# Sheet_2.net
KiCad netlist of a schematic drawn in Altium Designer
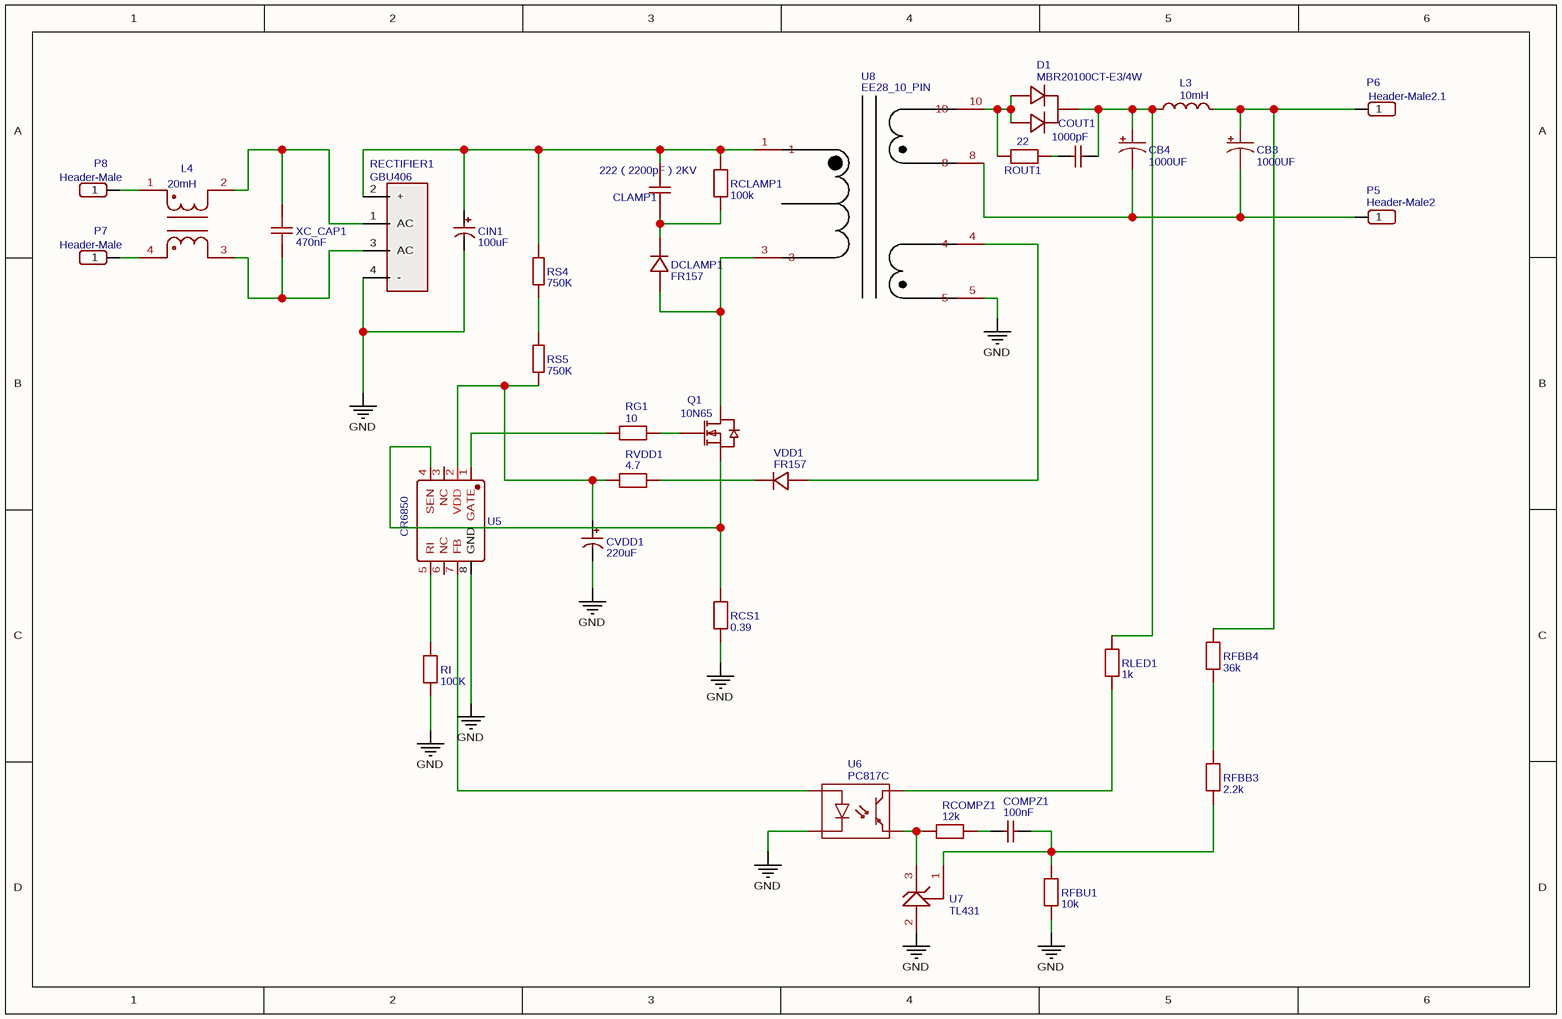
[diagram p0: Sheet_2.schdoc]

(export (version "E")
  (design (tool "Eeschema 10.0.6"))
  (components
    (comp (ref "CB3")
      (value "1000UF")
      (description "CAP-08070")
      (fields (field (name "CONTRIBUTOR") "SparkFun"))
      (libsource (lib "altium-import") (part "root_0_1000UF_"))
    )
    (comp (ref "CB4")
      (value "1000UF")
      (description "CAP-08070")
      (fields (field (name "CONTRIBUTOR") "SparkFun"))
      (libsource (lib "altium-import") (part "root_0_1000UF_"))
    )
    (comp (ref "CIN1")
      (value "100uF")
      (fields
        (field (name "BOM_MANUFACTURER PART") "400V 100uF 18X30")
        (field (name "BOM_SUPPLIER PART") "C2767")
      )
      (libsource (lib "altium-import") (part "root_3_100uF_"))
    )
    (comp (ref "CLAMP1")
      (value "222（2200pF）2KV")
      (fields (field (name "BOM_SUPPLIER PART") "C24926"))
      (libsource (lib "altium-import") (part "root_1_222（2200pF）2KV_"))
    )
    (comp (ref "COMPZ1")
      (value "100nF")
      (fields
        (field (name "BOM_MANUFACTURER PART") "104/100V 20%")
        (field (name "BOM_SUPPLIER PART") "C26856")
      )
      (libsource (lib "altium-import") (part "root_0_100nF_"))
    )
    (comp (ref "COUT1")
      (value "1000pF")
      (fields
        (field (name "BOM_MANUFACTURER PART") "102M 400V Y5V")
        (field (name "BOM_SUPPLIER PART") "C3704")
      )
      (libsource (lib "altium-import") (part "root_0_1000pF_"))
    )
    (comp (ref "CVDD1")
      (value "220uF")
      (fields (field (name "BOM_MANUFACTURER PART") "220uf/35V") (field (name "BOM_SUPPLIER PART") "C2063"))
      (libsource (lib "altium-import") (part "root_3_220uF_"))
    )
    (comp (ref "D1")
      (value "MBR20100CT-E3/4W")
      (fields (field (name "BOM_SUPPLIER PART") "C222466") (field (name "CONTRIBUTOR") "LCSC"))
      (libsource (lib "altium-import") (part "root_3_MBR20100CT-E3/4W_"))
    )
    (comp (ref "DCLAMP1")
      (value "FR157")
      (fields (field (name "BOM_SUPPLIER PART") "C2467"))
      (libsource (lib "altium-import") (part "root_1_FR157_"))
    )
    (comp (ref "L3")
      (value "10mH")
      (fields
        (field (name "BOM_MANUFACTURER PART") "VLU0608-103K")
        (field (name "BOM_SUPPLIER PART") "C72613")
      )
      (libsource (lib "altium-import") (part "root_0_10mH_"))
    )
    (comp (ref "L4")
      (value "20mH")
      (fields
        (field (name "BOM_SUPPLIER PART") "C148474")
        (field (name "BOM_MANUFACTURER PART") "UU9.8-10mH")
        (field (name "CONTRIBUTOR") "LCSC")
      )
      (libsource (lib "altium-import") (part "root_0_20mH_"))
    )
    (comp (ref "P5")
      (value "Header-Male2")
      (fields
        (field (name "BOM_MANUFACTURER PART") "Header-Male-2.54_1x1")
        (field (name "BOM_SUPPLIER PART") "C81276")
      )
      (libsource (lib "altium-import") (part "root_0_Header-Male2_"))
    )
    (comp (ref "P6")
      (value "Header-Male2.1")
      (fields
        (field (name "BOM_MANUFACTURER PART") "Header-Male-2.54_1x1")
        (field (name "BOM_SUPPLIER PART") "C81276")
      )
      (libsource (lib "altium-import") (part "root_0_Header-Male2.1_"))
    )
    (comp (ref "P7")
      (value "Header-Male")
      (fields
        (field (name "BOM_MANUFACTURER PART") "Header-Male-2.54_1x1")
        (field (name "BOM_SUPPLIER PART") "C81276")
      )
      (libsource (lib "altium-import") (part "root_2_Header-Male_"))
    )
    (comp (ref "P8")
      (value "Header-Male")
      (fields
        (field (name "BOM_MANUFACTURER PART") "Header-Male-2.54_1x1")
        (field (name "BOM_SUPPLIER PART") "C81276")
      )
      (libsource (lib "altium-import") (part "root_2_Header-Male_"))
    )
    (comp (ref "Q1")
      (value "10N65")
      (fields
        (field (name "BOM_MANUFACTURER PART") "10N65KL-TF3-T")
        (field (name "BOM_SUPPLIER PART") "C74166")
      )
      (libsource (lib "altium-import") (part "root_0_10N65_"))
    )
    (comp (ref "RCLAMP1") (value "100k") (libsource (lib "altium-import") (part "root_1_100k_")))
    (comp (ref "RCOMPZ1") (value "12k") (libsource (lib "altium-import") (part "root_0_12k_")))
    (comp (ref "RCS1") (value "0.39") (libsource (lib "altium-import") (part "root_1_0.39_")))
    (comp (ref "RECTIFIER1")
      (value "GBU406")
      (fields
        (field (name "BOM_MANUFACTURER PART") "GBU406 Rectifier bridge")
        (field (name "BOM_SUPPLIER PART") "C13432")
      )
      (libsource (lib "altium-import") (part "root_3_GBU406_"))
    )
    (comp (ref "RFBB3") (value "2.2k") (libsource (lib "altium-import") (part "root_1_2.2k_")))
    (comp (ref "RFBB4") (value "36k") (libsource (lib "altium-import") (part "root_1_36k_")))
    (comp (ref "RFBU1") (value "10k") (libsource (lib "altium-import") (part "root_1_10k_")))
    (comp (ref "RG1") (value "10") (libsource (lib "altium-import") (part "root_0_10_")))
    (comp (ref "RI") (value "100K") (libsource (lib "altium-import") (part "root_1_100K_")))
    (comp (ref "RLED1") (value "1k") (libsource (lib "altium-import") (part "root_1_1k_")))
    (comp (ref "ROUT1") (value "22") (libsource (lib "altium-import") (part "root_0_22_")))
    (comp (ref "RS4")
      (value "750K")
      (fields (field (name "BOM_SUPPLIER PART") "C119386") (field (name "CONTRIBUTOR") "LCSC"))
      (libsource (lib "altium-import") (part "root_1_750K_"))
    )
    (comp (ref "RS5")
      (value "750K")
      (fields (field (name "BOM_SUPPLIER PART") "C119386") (field (name "CONTRIBUTOR") "LCSC"))
      (libsource (lib "altium-import") (part "root_1_750K_"))
    )
    (comp (ref "RVDD1") (value "4.7") (libsource (lib "altium-import") (part "root_0_4.7_")))
    (comp (ref "U5")
      (value "CR6850")
      (fields
        (field (name "BOM_SUPPLIER PART") "C433346")
        (field (name "BOM_MANUFACTURER PART") "CR6850D")
        (field (name "CONTRIBUTOR") "LCSC")
      )
      (libsource (lib "altium-import") (part "root_3_CR6850_"))
    )
    (comp (ref "U6") (value "PC817C") (libsource (lib "altium-import") (part "root_0_PC817C_")))
    (comp (ref "U7")
      (value "TL431")
      (fields
        (field (name "BOM_MANUFACTURER PART") "TL431AILP")
        (field (name "BOM_SUPPLIER PART") "C72108")
        (field (name "CONTRIBUTOR") "LCSC")
      )
      (libsource (lib "altium-import") (part "root_1_TL431_"))
    )
    (comp (ref "U8")
      (value "EE28_10_PIN")
      (fields (field (name "BOM_SUPPLIER PART") "undefined") (field (name "CONTRIBUTOR") "kevwe"))
      (libsource (lib "altium-import") (part "root_0_EE28_10_PIN_"))
    )
    (comp (ref "VDD1")
      (value "FR157")
      (fields (field (name "BOM_SUPPLIER PART") "C2467"))
      (libsource (lib "altium-import") (part "root_2_FR157_"))
    )
    (comp (ref "XC_CAP1")
      (value "470nF")
      (fields (field (name "BOM_SUPPLIER PART") "C281974") (field (name "CONTRIBUTOR") "LCSC"))
      (libsource (lib "altium-import") (part "root_0_470nF_"))
    )
  )
  (nets
    (net (code "1") (name "GND") (class "Default")
      (node (ref "CIN1") (pin "2") (pinfunction "2_2") (pintype "passive"))
      (node (ref "CVDD1") (pin "2") (pinfunction "2_2") (pintype "passive"))
      (node (ref "RCS1") (pin "1") (pinfunction "1_1") (pintype "passive"))
      (node (ref "RECTIFIER1") (pin "4") (pinfunction "-_4") (pintype "passive"))
      (node (ref "RFBU1") (pin "1") (pinfunction "1_1") (pintype "passive"))
      (node (ref "RI") (pin "1") (pinfunction "1_1") (pintype "passive"))
      (node (ref "U5") (pin "8") (pinfunction "GND_8") (pintype "passive"))
      (node (ref "U6") (pin "2") (pinfunction "K_2") (pintype "passive"))
      (node (ref "U7") (pin "2") (pinfunction "ANODE_2") (pintype "passive"))
      (node (ref "U8") (pin "5") (pinfunction "5_5") (pintype "passive"))
    )
    (net (code "2") (name "Net-(CB3-Pad+)") (class "Default")
      (node (ref "CB3") (pin "+") (pinfunction "+_+") (pintype "passive"))
      (node (ref "L3") (pin "2") (pinfunction "2_2") (pintype "passive"))
      (node (ref "P6") (pin "1") (pinfunction "1_1") (pintype "passive"))
      (node (ref "RFBB4") (pin "2") (pinfunction "2_2") (pintype "passive"))
    )
    (net (code "3") (name "Net-(CB3-Pad-)") (class "Default")
      (node (ref "CB3") (pin "-") (pinfunction "-_-") (pintype "passive"))
      (node (ref "CB4") (pin "-") (pinfunction "-_-") (pintype "passive"))
      (node (ref "P5") (pin "1") (pinfunction "1_1") (pintype "passive"))
      (node (ref "U8") (pin "8") (pinfunction "8_8") (pintype "passive"))
    )
    (net (code "4") (name "Net-(CB4-Pad+)") (class "Default")
      (node (ref "CB4") (pin "+") (pinfunction "+_+") (pintype "passive"))
      (node (ref "COUT1") (pin "2") (pinfunction "2_2") (pintype "passive"))
      (node (ref "D1") (pin "2") (pinfunction "2_2") (pintype "passive"))
      (node (ref "L3") (pin "1") (pinfunction "1_1") (pintype "passive"))
      (node (ref "RLED1") (pin "2") (pinfunction "2_2") (pintype "passive"))
    )
    (net (code "5") (name "Net-(COMPZ1-Pad1)") (class "Default")
      (node (ref "COMPZ1") (pin "1") (pinfunction "1_1") (pintype "passive"))
      (node (ref "RCOMPZ1") (pin "2") (pinfunction "2_2") (pintype "passive"))
    )
    (net (code "6") (name "Net-(COUT1-Pad1)") (class "Default")
      (node (ref "COUT1") (pin "1") (pinfunction "1_1") (pintype "passive"))
      (node (ref "ROUT1") (pin "2") (pinfunction "2_2") (pintype "passive"))
    )
    (net (code "7") (name "Net-(D1-Pad1)") (class "Default")
      (node (ref "D1") (pin "1") (pinfunction "1_1") (pintype "passive"))
      (node (ref "D1") (pin "3") (pinfunction "3_3") (pintype "passive"))
      (node (ref "ROUT1") (pin "1") (pinfunction "1_1") (pintype "passive"))
      (node (ref "U8") (pin "10") (pinfunction "10_10") (pintype "passive"))
    )
    (net (code "8") (name "Net-(DCLAMP1-A)") (class "Default")
      (node (ref "DCLAMP1") (pin "1") (pinfunction "A_1") (pintype "passive"))
      (node (ref "Q1") (pin "2") (pinfunction "D_2") (pintype "passive"))
      (node (ref "U8") (pin "3") (pinfunction "3_3") (pintype "passive"))
    )
    (net (code "9") (name "Net-(DCLAMP1-K)") (class "Default")
      (node (ref "CLAMP1") (pin "1") (pinfunction "1_1") (pintype "passive"))
      (node (ref "DCLAMP1") (pin "2") (pinfunction "K_2") (pintype "passive"))
      (node (ref "RCLAMP1") (pin "1") (pinfunction "1_1") (pintype "passive"))
    )
    (net (code "10") (name "Net-(L4-Pad1)") (class "Default")
      (node (ref "L4") (pin "1") (pinfunction "1_1") (pintype "passive"))
      (node (ref "P8") (pin "1") (pinfunction "1_1") (pintype "passive"))
    )
    (net (code "11") (name "Net-(L4-Pad2)") (class "Default")
      (node (ref "L4") (pin "2") (pinfunction "2_2") (pintype "passive"))
      (node (ref "RECTIFIER1") (pin "1") (pinfunction "AC_1") (pintype "passive"))
      (node (ref "XC_CAP1") (pin "1") (pinfunction "1_1") (pintype "passive"))
    )
    (net (code "12") (name "Net-(L4-Pad3)") (class "Default")
      (node (ref "L4") (pin "3") (pinfunction "3_3") (pintype "passive"))
      (node (ref "RECTIFIER1") (pin "3") (pinfunction "AC_3") (pintype "passive"))
      (node (ref "XC_CAP1") (pin "2") (pinfunction "2_2") (pintype "passive"))
    )
    (net (code "13") (name "Net-(L4-Pad4)") (class "Default")
      (node (ref "L4") (pin "4") (pinfunction "4_4") (pintype "passive"))
      (node (ref "P7") (pin "1") (pinfunction "1_1") (pintype "passive"))
    )
    (net (code "14") (name "Net-(Q1-G)") (class "Default")
      (node (ref "Q1") (pin "1") (pinfunction "G_1") (pintype "passive"))
      (node (ref "RG1") (pin "2") (pinfunction "2_2") (pintype "passive"))
    )
    (net (code "15") (name "Net-(Q1-S)") (class "Default")
      (node (ref "Q1") (pin "3") (pinfunction "S_3") (pintype "passive"))
      (node (ref "RCS1") (pin "2") (pinfunction "2_2") (pintype "passive"))
      (node (ref "U5") (pin "4") (pinfunction "SEN_4") (pintype "passive"))
    )
    (net (code "16") (name "Net-(RECTIFIER1-+)") (class "Default")
      (node (ref "CIN1") (pin "1") (pinfunction "1_1") (pintype "passive"))
      (node (ref "CLAMP1") (pin "2") (pinfunction "2_2") (pintype "passive"))
      (node (ref "RCLAMP1") (pin "2") (pinfunction "2_2") (pintype "passive"))
      (node (ref "RECTIFIER1") (pin "2") (pinfunction "+_2") (pintype "passive"))
      (node (ref "RS4") (pin "2") (pinfunction "2_2") (pintype "passive"))
      (node (ref "U8") (pin "1") (pinfunction "1_1") (pintype "passive"))
    )
    (net (code "17") (name "Net-(RFBB3-Pad2)") (class "Default")
      (node (ref "RFBB3") (pin "2") (pinfunction "2_2") (pintype "passive"))
      (node (ref "RFBB4") (pin "1") (pinfunction "1_1") (pintype "passive"))
    )
    (net (code "18") (name "Net-(RS4-Pad1)") (class "Default")
      (node (ref "RS4") (pin "1") (pinfunction "1_1") (pintype "passive"))
      (node (ref "RS5") (pin "2") (pinfunction "2_2") (pintype "passive"))
    )
    (net (code "19") (name "Net-(U5-FB)") (class "Default")
      (node (ref "U5") (pin "7") (pinfunction "FB_7") (pintype "passive"))
      (node (ref "U6") (pin "1") (pinfunction "A_1") (pintype "passive"))
    )
    (net (code "20") (name "Net-(U5-GATE)") (class "Default")
      (node (ref "RG1") (pin "1") (pinfunction "1_1") (pintype "passive"))
      (node (ref "U5") (pin "1") (pinfunction "GATE_1") (pintype "passive"))
    )
    (net (code "21") (name "Net-(U5-RI)") (class "Default")
      (node (ref "RI") (pin "2") (pinfunction "2_2") (pintype "passive"))
      (node (ref "U5") (pin "5") (pinfunction "RI_5") (pintype "passive"))
    )
    (net (code "22") (name "Net-(U5-VDD)") (class "Default")
      (node (ref "CVDD1") (pin "1") (pinfunction "1_1") (pintype "passive"))
      (node (ref "RS5") (pin "1") (pinfunction "1_1") (pintype "passive"))
      (node (ref "RVDD1") (pin "1") (pinfunction "1_1") (pintype "passive"))
      (node (ref "U5") (pin "2") (pinfunction "VDD_2") (pintype "passive"))
    )
    (net (code "23") (name "Net-(U6-C)") (class "Default")
      (node (ref "RLED1") (pin "1") (pinfunction "1_1") (pintype "passive"))
      (node (ref "U6") (pin "4") (pinfunction "C_4") (pintype "passive"))
    )
    (net (code "24") (name "Net-(U6-E)") (class "Default")
      (node (ref "RCOMPZ1") (pin "1") (pinfunction "1_1") (pintype "passive"))
      (node (ref "U6") (pin "3") (pinfunction "E_3") (pintype "passive"))
      (node (ref "U7") (pin "3") (pinfunction "CATHODE_3") (pintype "passive"))
    )
    (net (code "25") (name "Net-(U7-REF)") (class "Default")
      (node (ref "COMPZ1") (pin "2") (pinfunction "2_2") (pintype "passive"))
      (node (ref "RFBB3") (pin "1") (pinfunction "1_1") (pintype "passive"))
      (node (ref "RFBU1") (pin "2") (pinfunction "2_2") (pintype "passive"))
      (node (ref "U7") (pin "1") (pinfunction "REF_1") (pintype "passive"))
    )
    (net (code "26") (name "Net-(VDD1-A)") (class "Default")
      (node (ref "U8") (pin "4") (pinfunction "4_4") (pintype "passive"))
      (node (ref "VDD1") (pin "1") (pinfunction "A_1") (pintype "passive"))
    )
    (net (code "27") (name "Net-(VDD1-K)") (class "Default")
      (node (ref "RVDD1") (pin "2") (pinfunction "2_2") (pintype "passive"))
      (node (ref "VDD1") (pin "2") (pinfunction "K_2") (pintype "passive"))
    )
    (net (code "28") (name "unconnected-(U5-NC-Pad3)") (class "Default")
      (node (ref "U5") (pin "3") (pinfunction "NC_3") (pintype "passive"))
    )
    (net (code "29") (name "unconnected-(U5-NC-Pad6)") (class "Default")
      (node (ref "U5") (pin "6") (pinfunction "NC_6") (pintype "passive"))
    )
  )
)
